# ArtFire.net
KiCad netlist of a schematic drawn in Altium Designer
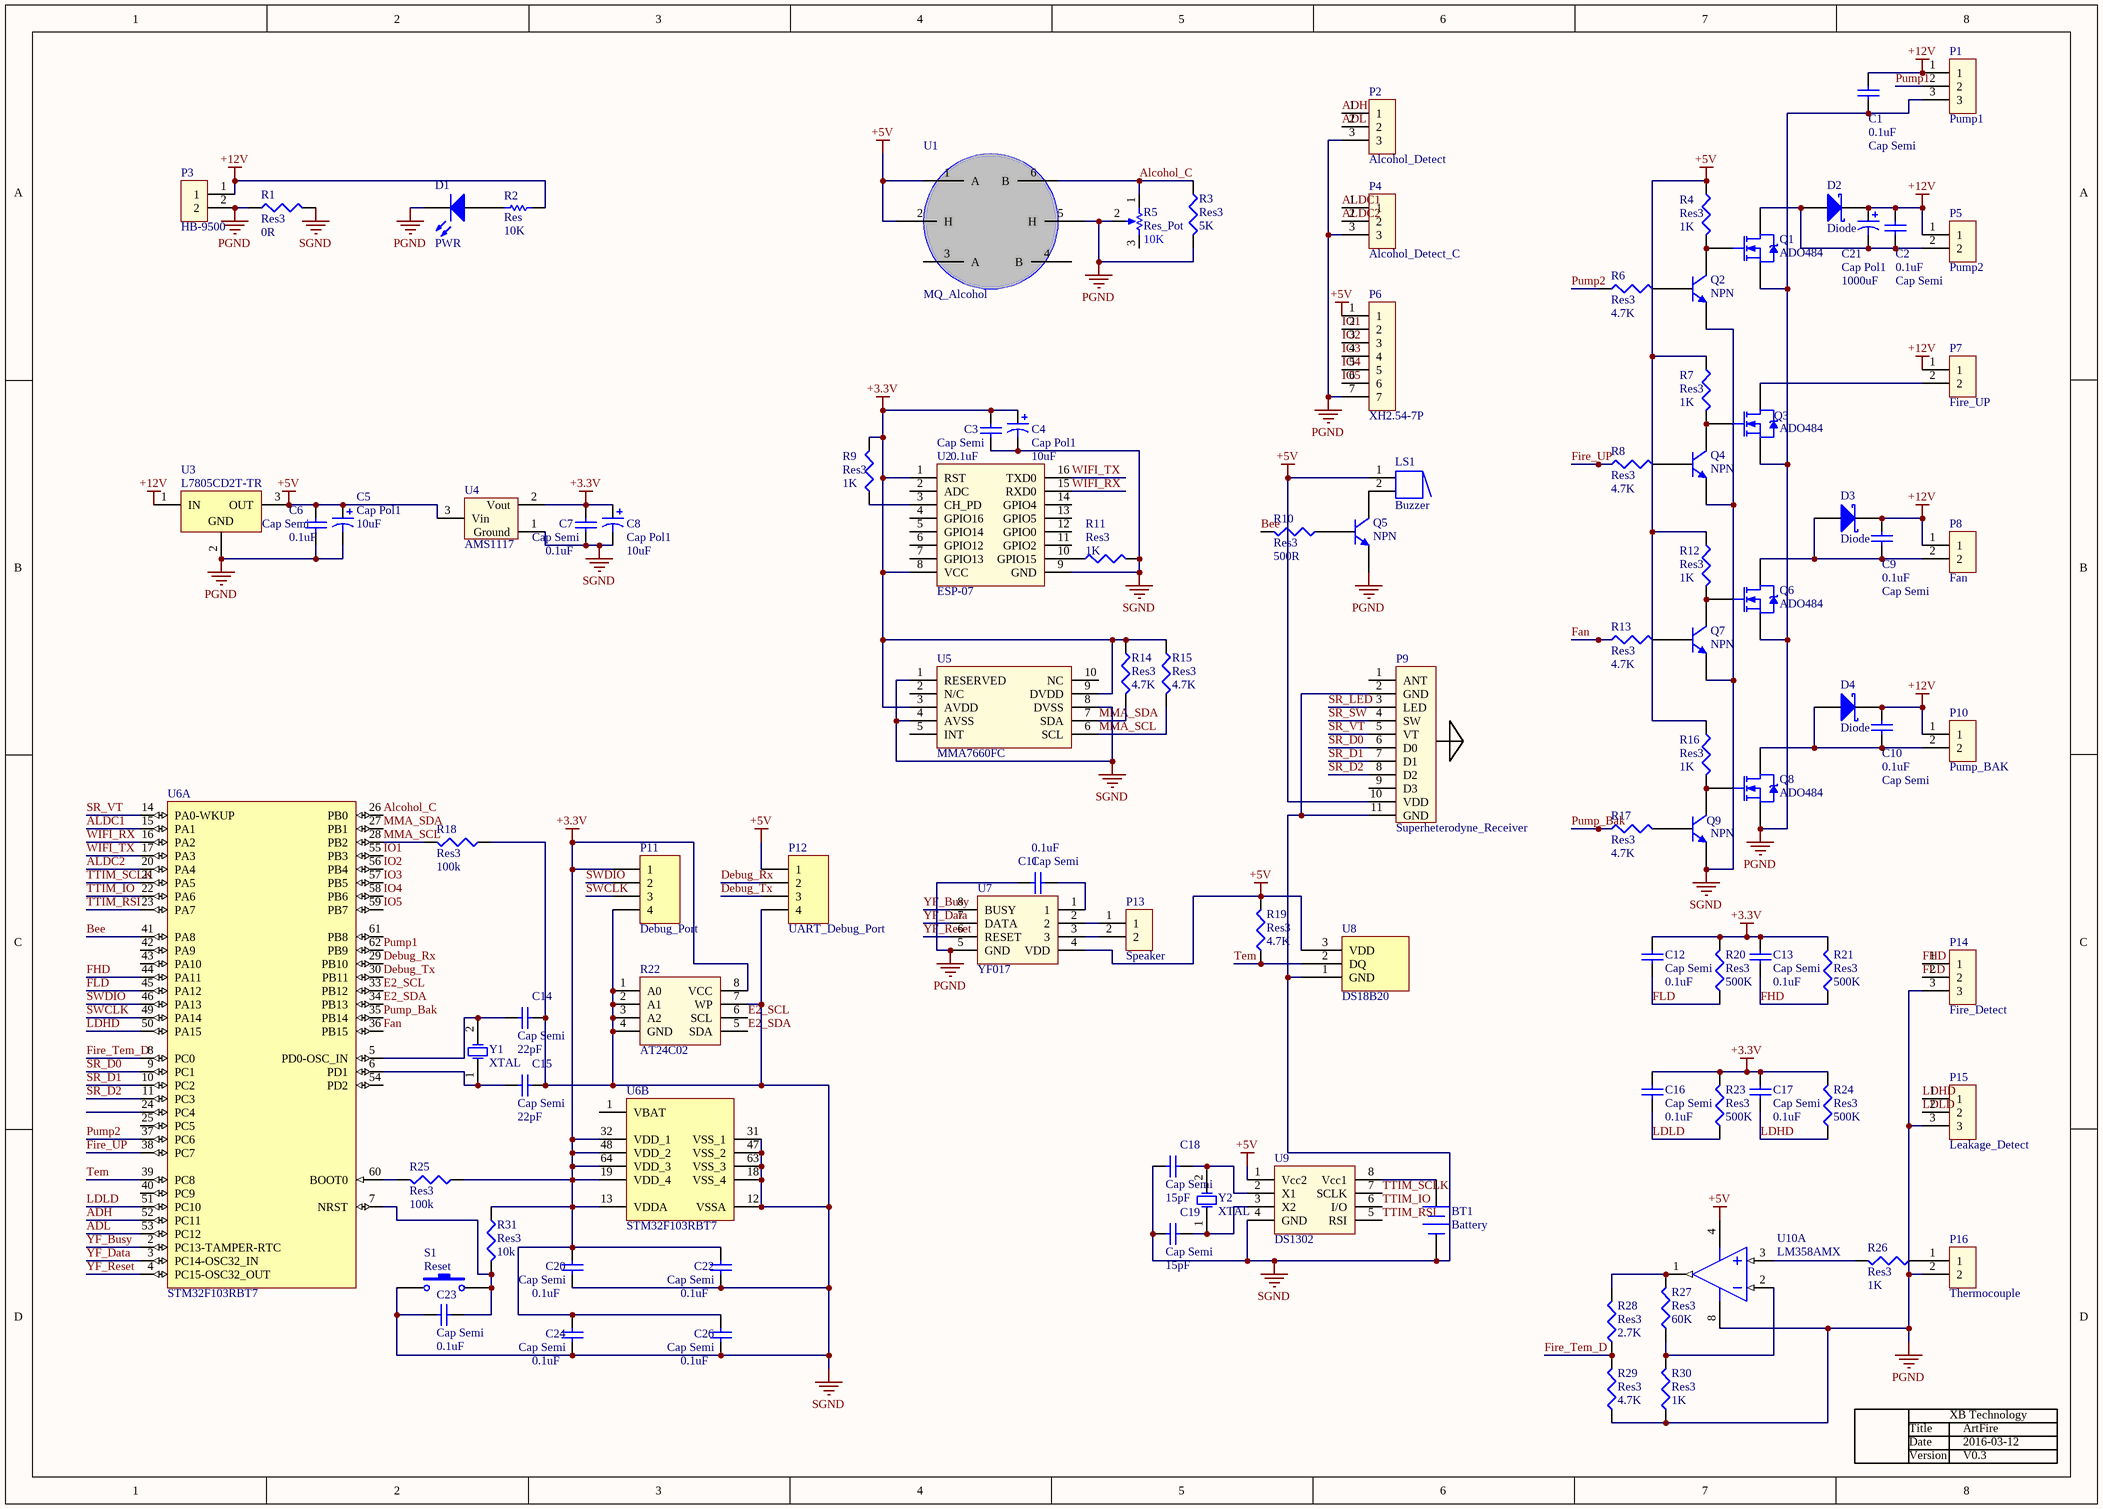
[diagram p0: ArtFire.SchDoc]

(export (version "E")
  (design (tool "Eeschema 10.0.6"))
  (components
    (comp (ref "BT1")
      (value "Battery")
      (footprint "Battery_1302")
      (description "Multicell Battery")
      (fields (field (name "PUBLISHER") "Altium Limited"))
      (libsource (lib "Miscellaneous Devices") (part "Battery"))
    )
    (comp (ref "C1")
      (value "Cap Semi")
      (footprint "6-0805_N")
      (description "Capacitor (Semiconductor SIM Model)")
      (fields (field (name "ALTIUM_VALUE") "0.1uF") (field (name "PUBLISHER") "Altium Limited"))
      (libsource (lib "Miscellaneous Devices") (part "Cap Semi"))
    )
    (comp (ref "C2")
      (value "Cap Semi")
      (footprint "6-0805_N")
      (description "Capacitor (Semiconductor SIM Model)")
      (fields (field (name "ALTIUM_VALUE") "0.1uF") (field (name "PUBLISHER") "Altium Limited"))
      (libsource (lib "Miscellaneous Devices") (part "Cap Semi"))
    )
    (comp (ref "C3")
      (value "Cap Semi")
      (footprint "6-0805_N")
      (description "Capacitor (Semiconductor SIM Model)")
      (fields (field (name "ALTIUM_VALUE") "0.1uF") (field (name "PUBLISHER") "Altium Limited"))
      (libsource (lib "Miscellaneous Devices") (part "Cap Semi"))
    )
    (comp (ref "C4")
      (value "Cap Pol1")
      (footprint "Cap_5*4mm")
      (description "Polarized Capacitor (Radial)")
      (fields (field (name "ALTIUM_VALUE") "10uF") (field (name "PUBLISHER") "Altium Limited"))
      (libsource (lib "Miscellaneous Devices") (part "Cap Pol1"))
    )
    (comp (ref "C5")
      (value "Cap Pol1")
      (footprint "Cap_5*4mm")
      (description "Polarized Capacitor (Radial)")
      (fields (field (name "ALTIUM_VALUE") "10uF") (field (name "PUBLISHER") "Altium Limited"))
      (libsource (lib "Miscellaneous Devices") (part "Cap Pol1"))
    )
    (comp (ref "C6")
      (value "Cap Semi")
      (footprint "6-0805_N")
      (description "Capacitor (Semiconductor SIM Model)")
      (fields (field (name "ALTIUM_VALUE") "0.1uF") (field (name "PUBLISHER") "Altium Limited"))
      (libsource (lib "Miscellaneous Devices") (part "Cap Semi"))
    )
    (comp (ref "C7")
      (value "Cap Semi")
      (footprint "6-0805_N")
      (description "Capacitor (Semiconductor SIM Model)")
      (fields (field (name "ALTIUM_VALUE") "0.1uF") (field (name "PUBLISHER") "Altium Limited"))
      (libsource (lib "Miscellaneous Devices") (part "Cap Semi"))
    )
    (comp (ref "C8")
      (value "Cap Pol1")
      (footprint "Cap_5*4mm")
      (description "Polarized Capacitor (Radial)")
      (fields (field (name "ALTIUM_VALUE") "10uF") (field (name "PUBLISHER") "Altium Limited"))
      (libsource (lib "Miscellaneous Devices") (part "Cap Pol1"))
    )
    (comp (ref "C9")
      (value "Cap Semi")
      (footprint "6-0805_N")
      (description "Capacitor (Semiconductor SIM Model)")
      (fields (field (name "ALTIUM_VALUE") "0.1uF") (field (name "PUBLISHER") "Altium Limited"))
      (libsource (lib "Miscellaneous Devices") (part "Cap Semi"))
    )
    (comp (ref "C10")
      (value "Cap Semi")
      (footprint "6-0805_N")
      (description "Capacitor (Semiconductor SIM Model)")
      (fields (field (name "ALTIUM_VALUE") "0.1uF") (field (name "PUBLISHER") "Altium Limited"))
      (libsource (lib "Miscellaneous Devices") (part "Cap Semi"))
    )
    (comp (ref "C11")
      (value "Cap Semi")
      (footprint "6-0805_N")
      (description "Capacitor (Semiconductor SIM Model)")
      (fields (field (name "ALTIUM_VALUE") "0.1uF") (field (name "PUBLISHER") "Altium Limited"))
      (libsource (lib "Miscellaneous Devices") (part "Cap Semi"))
    )
    (comp (ref "C12")
      (value "Cap Semi")
      (footprint "6-0805_N")
      (description "Capacitor (Semiconductor SIM Model)")
      (fields (field (name "ALTIUM_VALUE") "0.1uF") (field (name "PUBLISHER") "Altium Limited"))
      (libsource (lib "Miscellaneous Devices") (part "Cap Semi"))
    )
    (comp (ref "C13")
      (value "Cap Semi")
      (footprint "6-0805_N")
      (description "Capacitor (Semiconductor SIM Model)")
      (fields (field (name "ALTIUM_VALUE") "0.1uF") (field (name "PUBLISHER") "Altium Limited"))
      (libsource (lib "Miscellaneous Devices") (part "Cap Semi"))
    )
    (comp (ref "C14")
      (value "Cap Semi")
      (footprint "6-0805_N")
      (description "Capacitor (Semiconductor SIM Model)")
      (fields (field (name "ALTIUM_VALUE") "22pF") (field (name "PUBLISHER") "Altium Limited"))
      (libsource (lib "Miscellaneous Devices") (part "Cap Semi"))
    )
    (comp (ref "C15")
      (value "Cap Semi")
      (footprint "6-0805_N")
      (description "Capacitor (Semiconductor SIM Model)")
      (fields (field (name "ALTIUM_VALUE") "22pF") (field (name "PUBLISHER") "Altium Limited"))
      (libsource (lib "Miscellaneous Devices") (part "Cap Semi"))
    )
    (comp (ref "C16")
      (value "Cap Semi")
      (footprint "6-0805_N")
      (description "Capacitor (Semiconductor SIM Model)")
      (fields (field (name "ALTIUM_VALUE") "0.1uF") (field (name "PUBLISHER") "Altium Limited"))
      (libsource (lib "Miscellaneous Devices") (part "Cap Semi"))
    )
    (comp (ref "C17")
      (value "Cap Semi")
      (footprint "6-0805_N")
      (description "Capacitor (Semiconductor SIM Model)")
      (fields (field (name "ALTIUM_VALUE") "0.1uF") (field (name "PUBLISHER") "Altium Limited"))
      (libsource (lib "Miscellaneous Devices") (part "Cap Semi"))
    )
    (comp (ref "C18")
      (value "Cap Semi")
      (footprint "6-0805_N")
      (description "Capacitor (Semiconductor SIM Model)")
      (fields (field (name "ALTIUM_VALUE") "15pF") (field (name "PUBLISHER") "Altium Limited"))
      (libsource (lib "Miscellaneous Devices") (part "Cap Semi"))
    )
    (comp (ref "C19")
      (value "Cap Semi")
      (footprint "6-0805_N")
      (description "Capacitor (Semiconductor SIM Model)")
      (fields (field (name "ALTIUM_VALUE") "15pF") (field (name "PUBLISHER") "Altium Limited"))
      (libsource (lib "Miscellaneous Devices") (part "Cap Semi"))
    )
    (comp (ref "C20")
      (value "Cap Semi")
      (footprint "6-0805_N")
      (description "Capacitor (Semiconductor SIM Model)")
      (fields (field (name "ALTIUM_VALUE") "0.1uF") (field (name "PUBLISHER") "Altium Limited"))
      (libsource (lib "Miscellaneous Devices") (part "Cap Semi"))
    )
    (comp (ref "C21")
      (value "Cap Pol1")
      (footprint "CAP_10*10MM")
      (description "Polarized Capacitor (Radial)")
      (fields (field (name "ALTIUM_VALUE") "1000uF") (field (name "PUBLISHER") "Altium Limited"))
      (libsource (lib "Miscellaneous Devices") (part "Cap Pol1"))
    )
    (comp (ref "C22")
      (value "Cap Semi")
      (footprint "6-0805_N")
      (description "Capacitor (Semiconductor SIM Model)")
      (fields (field (name "ALTIUM_VALUE") "0.1uF") (field (name "PUBLISHER") "Altium Limited"))
      (libsource (lib "Miscellaneous Devices") (part "Cap Semi"))
    )
    (comp (ref "C23")
      (value "Cap Semi")
      (footprint "6-0805_N")
      (description "Capacitor (Semiconductor SIM Model)")
      (fields (field (name "ALTIUM_VALUE") "0.1uF") (field (name "PUBLISHER") "Altium Limited"))
      (libsource (lib "Miscellaneous Devices") (part "Cap Semi"))
    )
    (comp (ref "C24")
      (value "Cap Semi")
      (footprint "6-0805_N")
      (description "Capacitor (Semiconductor SIM Model)")
      (fields (field (name "ALTIUM_VALUE") "0.1uF") (field (name "PUBLISHER") "Altium Limited"))
      (libsource (lib "Miscellaneous Devices") (part "Cap Semi"))
    )
    (comp (ref "C26")
      (value "Cap Semi")
      (footprint "6-0805_N")
      (description "Capacitor (Semiconductor SIM Model)")
      (fields (field (name "ALTIUM_VALUE") "0.1uF") (field (name "PUBLISHER") "Altium Limited"))
      (libsource (lib "Miscellaneous Devices") (part "Cap Semi"))
    )
    (comp (ref "D1")
      (value "PWR")
      (footprint "6-0805_N")
      (description "Typical INFRARED GaAs LED")
      (fields (field (name "PUBLISHER") "Altium Limited"))
      (libsource (lib "Miscellaneous Devices") (part "LED0"))
    )
    (comp (ref "D2")
      (value "Diode")
      (footprint "US1M")
      (description "Silicon RF Schottky Diode for Mixer Applications in the VHF/UHF Range")
      (fields (field (name "PUBLISHER") "Altium Limited"))
      (libsource (lib "Miscellaneous Devices") (part "Diode BAT17"))
    )
    (comp (ref "D3")
      (value "Diode")
      (footprint "US1M")
      (description "Silicon RF Schottky Diode for Mixer Applications in the VHF/UHF Range")
      (fields (field (name "PUBLISHER") "Altium Limited"))
      (libsource (lib "Miscellaneous Devices") (part "Diode BAT17"))
    )
    (comp (ref "D4")
      (value "Diode")
      (footprint "US1M")
      (description "Silicon RF Schottky Diode for Mixer Applications in the VHF/UHF Range")
      (fields (field (name "PUBLISHER") "Altium Limited"))
      (libsource (lib "Miscellaneous Devices") (part "Diode BAT17"))
    )
    (comp (ref "LS1")
      (value "Buzzer")
      (footprint "BUZZER")
      (description "Magnetic Transducer Buzzer")
      (fields (field (name "PUBLISHER") "Altium Limited"))
      (libsource (lib "Miscellaneous Devices") (part "Buzzer"))
    )
    (comp (ref "P1") (value "Pump1") (footprint "XH2.54-3P") (libsource (lib "XH2.54") (part "XH2.54-3P")))
    (comp (ref "P2")
      (value "Alcohol_Detect")
      (footprint "XH2.54-3P")
      (libsource (lib "XH2.54") (part "XH2.54-3P"))
    )
    (comp (ref "P3")
      (value "HB-9500")
      (footprint "HB-9500")
      (description "High current connector")
      (libsource (lib "Simon'Library") (part "HB-9500"))
    )
    (comp (ref "P4")
      (value "Alcohol_Detect_C")
      (footprint "XH2.54-3P")
      (libsource (lib "XH2.54") (part "XH2.54-3P"))
    )
    (comp (ref "P5") (value "Pump2") (footprint "CH3.96_2P") (libsource (lib "CH3.96") (part "CH3.96_2P")))
    (comp (ref "P6")
      (value "XH2.54-7P")
      (footprint "XH2.54-7P")
      (libsource (lib "XH2.54") (part "XH2.54-7P"))
    )
    (comp (ref "P7") (value "Fire_UP") (footprint "KF3.96_2P") (libsource (lib "KF3.96") (part "KF3.96")))
    (comp (ref "P8") (value "Fan") (footprint "XH2.54-2P") (libsource (lib "XH2.54") (part "XH2.54-2P")))
    (comp (ref "P9")
      (value "Superheterodyne_Receiver")
      (footprint "Sperheterodyne_Receiver")
      (libsource (lib "Simon'Library") (part "Superheterodyne_Receiver"))
    )
    (comp (ref "P10")
      (value "Pump_BAK")
      (footprint "CH3.96_2P")
      (libsource (lib "CH3.96") (part "CH3.96_2P"))
    )
    (comp (ref "P11")
      (value "Debug_Port")
      (footprint "HDR1X4")
      (description "Header, 4-Pin")
      (fields (field (name "PUBLISHER") "Altium Limited"))
      (libsource (lib "Miscellaneous Connectors") (part "Header 4"))
    )
    (comp (ref "P12")
      (value "UART_Debug_Port")
      (footprint "HDR1X4")
      (description "Header, 4-Pin")
      (fields (field (name "PUBLISHER") "Altium Limited"))
      (libsource (lib "Miscellaneous Connectors") (part "Header 4"))
    )
    (comp (ref "P13") (value "Speaker") (footprint "XH2.54-2P") (libsource (lib "XH2.54") (part "XH2.54-2P")))
    (comp (ref "P14")
      (value "Fire_Detect")
      (footprint "CH3.96_3P")
      (libsource (lib "CH3.96") (part "CH3.96_3P"))
    )
    (comp (ref "P15")
      (value "Leakage_Detect")
      (footprint "XH2.54-3P")
      (libsource (lib "XH2.54") (part "XH2.54-3P"))
    )
    (comp (ref "P16")
      (value "Thermocouple")
      (footprint "CH3.96_2P")
      (libsource (lib "CH3.96") (part "CH3.96_2P"))
    )
    (comp (ref "Q1")
      (value "ADO484")
      (footprint "D2PAK_N")
      (description "N-Channel Power MOSFET")
      (fields (field (name "PUBLISHER") "Altium Limited"))
      (libsource (lib "Miscellaneous Devices") (part "NMOS-2"))
    )
    (comp (ref "Q2")
      (value "NPN")
      (footprint "SOT-23_N")
      (description "NPN Bipolar Transistor")
      (fields (field (name "PUBLISHER") "Altium Limited"))
      (libsource (lib "Miscellaneous Devices") (part "NPN"))
    )
    (comp (ref "Q3")
      (value "ADO484")
      (footprint "D2PAK_N")
      (description "N-Channel Power MOSFET")
      (fields (field (name "PUBLISHER") "Altium Limited"))
      (libsource (lib "Miscellaneous Devices") (part "NMOS-2"))
    )
    (comp (ref "Q4")
      (value "NPN")
      (footprint "SOT-23_N")
      (description "NPN Bipolar Transistor")
      (fields (field (name "PUBLISHER") "Altium Limited"))
      (libsource (lib "Miscellaneous Devices") (part "NPN"))
    )
    (comp (ref "Q5")
      (value "NPN")
      (footprint "SOT-23_N")
      (description "NPN Bipolar Transistor")
      (fields (field (name "PUBLISHER") "Altium Limited"))
      (libsource (lib "Miscellaneous Devices") (part "NPN"))
    )
    (comp (ref "Q6")
      (value "ADO484")
      (footprint "D2PAK_N")
      (description "N-Channel Power MOSFET")
      (fields (field (name "PUBLISHER") "Altium Limited"))
      (libsource (lib "Miscellaneous Devices") (part "NMOS-2"))
    )
    (comp (ref "Q7")
      (value "NPN")
      (footprint "SOT-23_N")
      (description "NPN Bipolar Transistor")
      (fields (field (name "PUBLISHER") "Altium Limited"))
      (libsource (lib "Miscellaneous Devices") (part "NPN"))
    )
    (comp (ref "Q8")
      (value "ADO484")
      (footprint "D2PAK_N")
      (description "N-Channel Power MOSFET")
      (fields (field (name "PUBLISHER") "Altium Limited"))
      (libsource (lib "Miscellaneous Devices") (part "NMOS-2"))
    )
    (comp (ref "Q9")
      (value "NPN")
      (footprint "SOT-23_N")
      (description "NPN Bipolar Transistor")
      (fields (field (name "PUBLISHER") "Altium Limited"))
      (libsource (lib "Miscellaneous Devices") (part "NPN"))
    )
    (comp (ref "R1")
      (value "Res3")
      (footprint "6-0805_N")
      (description "Resistor")
      (fields (field (name "ALTIUM_VALUE") "0R") (field (name "PUBLISHER") "Altium Limited"))
      (libsource (lib "Miscellaneous Devices") (part "Res3"))
    )
    (comp (ref "R2")
      (value "Res")
      (footprint "6-0805_N")
      (description "Resistor")
      (fields (field (name "ALTIUM_VALUE") "10K") (field (name "PUBLISHER") "Altium Limited"))
      (libsource (lib "Miscellaneous Devices") (part "Res1"))
    )
    (comp (ref "R3")
      (value "Res3")
      (footprint "6-0805_N")
      (description "Resistor")
      (fields (field (name "ALTIUM_VALUE") "5K") (field (name "PUBLISHER") "Altium Limited"))
      (libsource (lib "Miscellaneous Devices") (part "Res3"))
    )
    (comp (ref "R4")
      (value "Res3")
      (footprint "6-0805_N")
      (description "Resistor")
      (fields (field (name "ALTIUM_VALUE") "1K") (field (name "PUBLISHER") "Altium Limited"))
      (libsource (lib "Miscellaneous Devices") (part "Res3"))
    )
    (comp (ref "R5")
      (value "Res_Pot")
      (footprint "VR5")
      (fields (field (name "RES_V") "10K"))
      (libsource (lib "Simon'Library") (part "Res_Pot"))
    )
    (comp (ref "R6")
      (value "Res3")
      (footprint "6-0805_N")
      (description "Resistor")
      (fields (field (name "ALTIUM_VALUE") "4.7K") (field (name "PUBLISHER") "Altium Limited"))
      (libsource (lib "Miscellaneous Devices") (part "Res3"))
    )
    (comp (ref "R7")
      (value "Res3")
      (footprint "6-0805_N")
      (description "Resistor")
      (fields (field (name "ALTIUM_VALUE") "1K") (field (name "PUBLISHER") "Altium Limited"))
      (libsource (lib "Miscellaneous Devices") (part "Res3"))
    )
    (comp (ref "R8")
      (value "Res3")
      (footprint "6-0805_N")
      (description "Resistor")
      (fields (field (name "ALTIUM_VALUE") "4.7K") (field (name "PUBLISHER") "Altium Limited"))
      (libsource (lib "Miscellaneous Devices") (part "Res3"))
    )
    (comp (ref "R9")
      (value "Res3")
      (footprint "6-0805_N")
      (description "Resistor")
      (fields (field (name "ALTIUM_VALUE") "1K") (field (name "PUBLISHER") "Altium Limited"))
      (libsource (lib "Miscellaneous Devices") (part "Res3"))
    )
    (comp (ref "R10")
      (value "Res3")
      (footprint "6-0805_N")
      (description "Resistor")
      (fields (field (name "ALTIUM_VALUE") "500R") (field (name "PUBLISHER") "Altium Limited"))
      (libsource (lib "Miscellaneous Devices") (part "Res3"))
    )
    (comp (ref "R11")
      (value "Res3")
      (footprint "6-0805_N")
      (description "Resistor")
      (fields (field (name "ALTIUM_VALUE") "1K") (field (name "PUBLISHER") "Altium Limited"))
      (libsource (lib "Miscellaneous Devices") (part "Res3"))
    )
    (comp (ref "R12")
      (value "Res3")
      (footprint "6-0805_N")
      (description "Resistor")
      (fields (field (name "ALTIUM_VALUE") "1K") (field (name "PUBLISHER") "Altium Limited"))
      (libsource (lib "Miscellaneous Devices") (part "Res3"))
    )
    (comp (ref "R13")
      (value "Res3")
      (footprint "6-0805_N")
      (description "Resistor")
      (fields (field (name "ALTIUM_VALUE") "4.7K") (field (name "PUBLISHER") "Altium Limited"))
      (libsource (lib "Miscellaneous Devices") (part "Res3"))
    )
    (comp (ref "R14")
      (value "Res3")
      (footprint "6-0805_N")
      (description "Resistor")
      (fields (field (name "ALTIUM_VALUE") "4.7K") (field (name "PUBLISHER") "Altium Limited"))
      (libsource (lib "Miscellaneous Devices") (part "Res3"))
    )
    (comp (ref "R15")
      (value "Res3")
      (footprint "6-0805_N")
      (description "Resistor")
      (fields (field (name "ALTIUM_VALUE") "4.7K") (field (name "PUBLISHER") "Altium Limited"))
      (libsource (lib "Miscellaneous Devices") (part "Res3"))
    )
    (comp (ref "R16")
      (value "Res3")
      (footprint "6-0805_N")
      (description "Resistor")
      (fields (field (name "ALTIUM_VALUE") "1K") (field (name "PUBLISHER") "Altium Limited"))
      (libsource (lib "Miscellaneous Devices") (part "Res3"))
    )
    (comp (ref "R17")
      (value "Res3")
      (footprint "6-0805_N")
      (description "Resistor")
      (fields (field (name "ALTIUM_VALUE") "4.7K") (field (name "PUBLISHER") "Altium Limited"))
      (libsource (lib "Miscellaneous Devices") (part "Res3"))
    )
    (comp (ref "R18")
      (value "Res3")
      (footprint "6-0805_N")
      (description "Resistor")
      (fields (field (name "ALTIUM_VALUE") "100k") (field (name "PUBLISHER") "Altium Limited"))
      (libsource (lib "Miscellaneous Devices") (part "Res3"))
    )
    (comp (ref "R19")
      (value "Res3")
      (footprint "6-0805_N")
      (description "Resistor")
      (fields (field (name "ALTIUM_VALUE") "4.7K") (field (name "PUBLISHER") "Altium Limited"))
      (libsource (lib "Miscellaneous Devices") (part "Res3"))
    )
    (comp (ref "R20")
      (value "Res3")
      (footprint "6-0805_N")
      (description "Resistor")
      (fields (field (name "ALTIUM_VALUE") "500K") (field (name "PUBLISHER") "Altium Limited"))
      (libsource (lib "Miscellaneous Devices") (part "Res3"))
    )
    (comp (ref "R21")
      (value "Res3")
      (footprint "6-0805_N")
      (description "Resistor")
      (fields (field (name "ALTIUM_VALUE") "500K") (field (name "PUBLISHER") "Altium Limited"))
      (libsource (lib "Miscellaneous Devices") (part "Res3"))
    )
    (comp (ref "R22")
      (value "AT24C02")
      (footprint "SOP8_TDA2822")
      (libsource (lib "Simon'Library") (part "AT24C02"))
    )
    (comp (ref "R23")
      (value "Res3")
      (footprint "6-0805_N")
      (description "Resistor")
      (fields (field (name "ALTIUM_VALUE") "500K") (field (name "PUBLISHER") "Altium Limited"))
      (libsource (lib "Miscellaneous Devices") (part "Res3"))
    )
    (comp (ref "R24")
      (value "Res3")
      (footprint "6-0805_N")
      (description "Resistor")
      (fields (field (name "ALTIUM_VALUE") "500K") (field (name "PUBLISHER") "Altium Limited"))
      (libsource (lib "Miscellaneous Devices") (part "Res3"))
    )
    (comp (ref "R25")
      (value "Res3")
      (footprint "6-0805_N")
      (description "Resistor")
      (fields (field (name "ALTIUM_VALUE") "100k") (field (name "PUBLISHER") "Altium Limited"))
      (libsource (lib "Miscellaneous Devices") (part "Res3"))
    )
    (comp (ref "R26")
      (value "Res3")
      (footprint "6-0805_N")
      (description "Resistor")
      (fields (field (name "ALTIUM_VALUE") "1K") (field (name "PUBLISHER") "Altium Limited"))
      (libsource (lib "Miscellaneous Devices") (part "Res3"))
    )
    (comp (ref "R27")
      (value "Res3")
      (footprint "6-0805_N")
      (description "Resistor")
      (fields (field (name "ALTIUM_VALUE") "60K") (field (name "PUBLISHER") "Altium Limited"))
      (libsource (lib "Miscellaneous Devices") (part "Res3"))
    )
    (comp (ref "R28")
      (value "Res3")
      (footprint "6-0805_N")
      (description "Resistor")
      (fields (field (name "ALTIUM_VALUE") "2.7K") (field (name "PUBLISHER") "Altium Limited"))
      (libsource (lib "Miscellaneous Devices") (part "Res3"))
    )
    (comp (ref "R29")
      (value "Res3")
      (footprint "6-0805_N")
      (description "Resistor")
      (fields (field (name "ALTIUM_VALUE") "4.7K") (field (name "PUBLISHER") "Altium Limited"))
      (libsource (lib "Miscellaneous Devices") (part "Res3"))
    )
    (comp (ref "R30")
      (value "Res3")
      (footprint "6-0805_N")
      (description "Resistor")
      (fields (field (name "ALTIUM_VALUE") "1K") (field (name "PUBLISHER") "Altium Limited"))
      (libsource (lib "Miscellaneous Devices") (part "Res3"))
    )
    (comp (ref "R31")
      (value "Res3")
      (footprint "6-0805_N")
      (description "Resistor")
      (fields (field (name "ALTIUM_VALUE") "10k") (field (name "PUBLISHER") "Altium Limited"))
      (libsource (lib "Miscellaneous Devices") (part "Res3"))
    )
    (comp (ref "S1")
      (value "Reset")
      (footprint "SWP_PB_6.5mm")
      (description "Switch")
      (fields (field (name "PUBLISHER") "Altium Limited"))
      (libsource (lib "Miscellaneous Devices") (part "SW-PB"))
    )
    (comp (ref "U1") (value "MQ_Alcohol") (footprint "MQ") (libsource (lib "Simon'Library") (part "MQ")))
    (comp (ref "U2")
      (value "ESP-07")
      (footprint "ESP-07_Wifi")
      (libsource (lib "Simon'Library") (part "ESP-07_Wifi"))
    )
    (comp (ref "U3")
      (value "L7805CD2T-TR")
      (footprint "D2PAK_N")
      (description "Positive Voltage Regulator, 5V, 3-Pin TO-220")
      (libsource (lib "altium-import") (part "root_0_PM-REG-L4940-SIL3_"))
    )
    (comp (ref "U4")
      (value "AMS1117")
      (footprint "SOT223_N")
      (libsource (lib "Simon'Library") (part "AMS1117"))
    )
    (comp (ref "U5")
      (value "MMA7660FC")
      (footprint "DFN-10P")
      (libsource (lib "Simon'Library") (part "MMA7660FC"))
    )
    (comp (ref "U6")
      (value "STM32F103RBT7")
      (footprint "LQFP64_L")
      (libsource (lib "Altium Content Vault") (part "MC-ARM-STM32F101-SQ64"))
    )
    (comp (ref "U7") (value "YF017") (footprint "DIP-8") (libsource (lib "Simon'Library") (part "YF017")))
    (comp (ref "U8")
      (value "DS18B20")
      (footprint "TO-92A")
      (libsource (lib "Simon'Library") (part "DS18B20"))
    )
    (comp (ref "U9")
      (value "DS1302")
      (footprint "SOP8_TDA2822")
      (libsource (lib "Simon'Library") (part "DS1302"))
    )
    (comp (ref "U10")
      (value "LM358AMX")
      (footprint "M08A_M")
      (description "Low Power Dual Operational Amplifier, 8-pin Narrow SOIC")
      (fields (field (name "MANUFACTURER") "National Semiconductor"))
      (libsource (lib "Altium Content Vault") (part "AMP-OPA-LM158-8"))
    )
    (comp (ref "Y1")
      (value "XTAL")
      (footprint "XTAL")
      (description "Crystal Oscillator")
      (fields (field (name "PUBLISHER") "Altium Limited"))
      (libsource (lib "Miscellaneous Devices") (part "XTAL"))
    )
    (comp (ref "Y2")
      (value "XTAL")
      (footprint "32.768Cystal")
      (description "Crystal Oscillator")
      (fields (field (name "PUBLISHER") "Altium Limited"))
      (libsource (lib "Miscellaneous Devices") (part "XTAL"))
    )
  )
  (nets
    (net (code "1") (name "+3.3V") (class "Default")
      (node (ref "C12") (pin "2") (pinfunction "2_2") (pintype "passive"))
      (node (ref "C13") (pin "2") (pinfunction "2_2") (pintype "passive"))
      (node (ref "C16") (pin "2") (pinfunction "2_2") (pintype "passive"))
      (node (ref "C17") (pin "2") (pinfunction "2_2") (pintype "passive"))
      (node (ref "C20") (pin "1") (pinfunction "1_1") (pintype "passive"))
      (node (ref "C22") (pin "1") (pinfunction "1_1") (pintype "passive"))
      (node (ref "C24") (pin "1") (pinfunction "1_1") (pintype "passive"))
      (node (ref "C26") (pin "1") (pinfunction "1_1") (pintype "passive"))
      (node (ref "C3") (pin "1") (pinfunction "1_1") (pintype "passive"))
      (node (ref "C4") (pin "1") (pinfunction "1_1") (pintype "passive"))
      (node (ref "C7") (pin "1") (pinfunction "1_1") (pintype "passive"))
      (node (ref "C8") (pin "1") (pinfunction "1_1") (pintype "passive"))
      (node (ref "P11") (pin "1") (pinfunction "1_1") (pintype "passive"))
      (node (ref "R14") (pin "1") (pinfunction "1_1") (pintype "passive"))
      (node (ref "R15") (pin "1") (pinfunction "1_1") (pintype "passive"))
      (node (ref "R20") (pin "2") (pinfunction "2_2") (pintype "passive"))
      (node (ref "R21") (pin "2") (pinfunction "2_2") (pintype "passive"))
      (node (ref "R22") (pin "8") (pinfunction "VCC_8") (pintype "passive"))
      (node (ref "R23") (pin "2") (pinfunction "2_2") (pintype "passive"))
      (node (ref "R24") (pin "2") (pinfunction "2_2") (pintype "passive"))
      (node (ref "R25") (pin "1") (pinfunction "1_1") (pintype "passive"))
      (node (ref "R31") (pin "1") (pinfunction "1_1") (pintype "passive"))
      (node (ref "R9") (pin "2") (pinfunction "2_2") (pintype "passive"))
      (node (ref "U2") (pin "1") (pinfunction "RST_1") (pintype "passive"))
      (node (ref "U2") (pin "8") (pinfunction "VCC_8") (pintype "passive"))
      (node (ref "U4") (pin "2") (pinfunction "Vout_2") (pintype "passive"))
      (node (ref "U5") (pin "3") (pinfunction "AVDD_3") (pintype "passive"))
      (node (ref "U5") (pin "9") (pinfunction "DVDD_9") (pintype "passive"))
      (node (ref "U6") (pin "13") (pinfunction "VDDA_13") (pintype "power_in"))
      (node (ref "U6") (pin "19") (pinfunction "VDD_4_19") (pintype "power_in"))
      (node (ref "U6") (pin "32") (pinfunction "VDD_1_32") (pintype "power_in"))
      (node (ref "U6") (pin "48") (pinfunction "VDD_2_48") (pintype "power_in"))
      (node (ref "U6") (pin "64") (pinfunction "VDD_3_64") (pintype "power_in"))
    )
    (net (code "2") (name "+5V") (class "Default")
      (node (ref "C5") (pin "1") (pinfunction "1_1") (pintype "passive"))
      (node (ref "C6") (pin "1") (pinfunction "1_1") (pintype "passive"))
      (node (ref "LS1") (pin "1") (pinfunction "1_1") (pintype "passive"))
      (node (ref "P12") (pin "1") (pinfunction "1_1") (pintype "passive"))
      (node (ref "P6") (pin "1") (pinfunction "1_1") (pintype "passive"))
      (node (ref "P9") (pin "10") (pinfunction "VDD_10") (pintype "passive"))
      (node (ref "R12") (pin "1") (pinfunction "1_1") (pintype "passive"))
      (node (ref "R16") (pin "1") (pinfunction "1_1") (pintype "passive"))
      (node (ref "R19") (pin "2") (pinfunction "2_2") (pintype "passive"))
      (node (ref "R4") (pin "1") (pinfunction "1_1") (pintype "passive"))
      (node (ref "R7") (pin "1") (pinfunction "1_1") (pintype "passive"))
      (node (ref "U1") (pin "1") (pinfunction "A_1") (pintype "passive"))
      (node (ref "U1") (pin "2") (pinfunction "H_2") (pintype "passive"))
      (node (ref "U10") (pin "4") (pinfunction "GND_4") (pintype "power_in"))
      (node (ref "U3") (pin "3") (pinfunction "OUT_3") (pintype "power_in"))
      (node (ref "U4") (pin "3") (pinfunction "Vin_3") (pintype "passive"))
      (node (ref "U7") (pin "4") (pinfunction "VDD_4") (pintype "passive"))
      (node (ref "U8") (pin "3") (pinfunction "VDD_3") (pintype "passive"))
      (node (ref "U9") (pin "1") (pinfunction "Vcc2_1") (pintype "passive"))
    )
    (net (code "3") (name "+12V") (class "Default")
      (node (ref "C1") (pin "1") (pinfunction "1_1") (pintype "passive"))
      (node (ref "C10") (pin "1") (pinfunction "1_1") (pintype "passive"))
      (node (ref "C2") (pin "1") (pinfunction "1_1") (pintype "passive"))
      (node (ref "C21") (pin "1") (pinfunction "1_1") (pintype "passive"))
      (node (ref "C9") (pin "1") (pinfunction "1_1") (pintype "passive"))
      (node (ref "D2") (pin "2") (pinfunction "K_2") (pintype "passive"))
      (node (ref "D3") (pin "2") (pinfunction "K_2") (pintype "passive"))
      (node (ref "D4") (pin "2") (pinfunction "K_2") (pintype "passive"))
      (node (ref "P1") (pin "1") (pinfunction "1_1") (pintype "passive"))
      (node (ref "P10") (pin "1") (pinfunction "1_1") (pintype "passive"))
      (node (ref "P3") (pin "1") (pinfunction "1_1") (pintype "passive"))
      (node (ref "P5") (pin "1") (pinfunction "1_1") (pintype "passive"))
      (node (ref "P7") (pin "1") (pinfunction "1_1") (pintype "passive"))
      (node (ref "P8") (pin "1") (pinfunction "1_1") (pintype "passive"))
      (node (ref "R2") (pin "2") (pinfunction "2_2") (pintype "passive"))
      (node (ref "U3") (pin "1") (pinfunction "IN_1") (pintype "power_in"))
    )
    (net (code "4") (name "/ADH") (class "Default")
      (node (ref "P2") (pin "1") (pinfunction "1_1") (pintype "passive"))
      (node (ref "U6") (pin "52") (pinfunction "PC11_52") (pintype "bidirectional"))
    )
    (net (code "5") (name "/ADL") (class "Default")
      (node (ref "P2") (pin "2") (pinfunction "2_2") (pintype "passive"))
      (node (ref "U6") (pin "53") (pinfunction "PC12_53") (pintype "bidirectional"))
    )
    (net (code "6") (name "/ALDC1") (class "Default")
      (node (ref "P4") (pin "1") (pinfunction "1_1") (pintype "passive"))
      (node (ref "U6") (pin "15") (pinfunction "PA1_15") (pintype "bidirectional"))
    )
    (net (code "7") (name "/ALDC2") (class "Default")
      (node (ref "P4") (pin "2") (pinfunction "2_2") (pintype "passive"))
      (node (ref "U6") (pin "20") (pinfunction "PA4_20") (pintype "bidirectional"))
    )
    (net (code "8") (name "/Alcohol_C") (class "Default")
      (node (ref "R3") (pin "1") (pinfunction "1_1") (pintype "passive"))
      (node (ref "R5") (pin "1") (pinfunction "TOP_1") (pintype "passive"))
      (node (ref "U1") (pin "6") (pinfunction "B_6") (pintype "passive"))
      (node (ref "U6") (pin "26") (pinfunction "PB0_26") (pintype "bidirectional"))
    )
    (net (code "9") (name "/Bee") (class "Default")
      (node (ref "R10") (pin "2") (pinfunction "2_2") (pintype "passive"))
      (node (ref "U6") (pin "41") (pinfunction "PA8_41") (pintype "bidirectional"))
    )
    (net (code "10") (name "/Debug_Rx") (class "Default")
      (node (ref "P12") (pin "2") (pinfunction "2_2") (pintype "passive"))
      (node (ref "U6") (pin "29") (pinfunction "PB10_29") (pintype "bidirectional"))
    )
    (net (code "11") (name "/Debug_Tx") (class "Default")
      (node (ref "P12") (pin "3") (pinfunction "3_3") (pintype "passive"))
      (node (ref "U6") (pin "30") (pinfunction "PB11_30") (pintype "bidirectional"))
    )
    (net (code "12") (name "/E2_SCL") (class "Default")
      (node (ref "R22") (pin "6") (pinfunction "SCL_6") (pintype "passive"))
      (node (ref "U6") (pin "33") (pinfunction "PB12_33") (pintype "bidirectional"))
    )
    (net (code "13") (name "/E2_SDA") (class "Default")
      (node (ref "R22") (pin "5") (pinfunction "SDA_5") (pintype "passive"))
      (node (ref "U6") (pin "34") (pinfunction "PB13_34") (pintype "bidirectional"))
    )
    (net (code "14") (name "/FHD") (class "Default")
      (node (ref "C13") (pin "1") (pinfunction "1_1") (pintype "passive"))
      (node (ref "P14") (pin "1") (pinfunction "1_1") (pintype "passive"))
      (node (ref "R21") (pin "1") (pinfunction "1_1") (pintype "passive"))
      (node (ref "U6") (pin "44") (pinfunction "PA11_44") (pintype "bidirectional"))
    )
    (net (code "15") (name "/FLD") (class "Default")
      (node (ref "C12") (pin "1") (pinfunction "1_1") (pintype "passive"))
      (node (ref "P14") (pin "2") (pinfunction "2_2") (pintype "passive"))
      (node (ref "R20") (pin "1") (pinfunction "1_1") (pintype "passive"))
      (node (ref "U6") (pin "45") (pinfunction "PA12_45") (pintype "bidirectional"))
    )
    (net (code "16") (name "/Fan") (class "Default")
      (node (ref "R13") (pin "1") (pinfunction "1_1") (pintype "passive"))
      (node (ref "U6") (pin "36") (pinfunction "PB15_36") (pintype "bidirectional"))
    )
    (net (code "17") (name "/Fire_Tem_D") (class "Default")
      (node (ref "R28") (pin "1") (pinfunction "1_1") (pintype "passive"))
      (node (ref "R29") (pin "2") (pinfunction "2_2") (pintype "passive"))
      (node (ref "U6") (pin "8") (pinfunction "PC0_8") (pintype "bidirectional"))
    )
    (net (code "18") (name "/Fire_UP") (class "Default")
      (node (ref "R8") (pin "1") (pinfunction "1_1") (pintype "passive"))
      (node (ref "U6") (pin "38") (pinfunction "PC7_38") (pintype "bidirectional"))
    )
    (net (code "19") (name "/IO1") (class "Default")
      (node (ref "P6") (pin "2") (pinfunction "2_2") (pintype "passive"))
      (node (ref "U6") (pin "55") (pinfunction "PB3_55") (pintype "bidirectional"))
    )
    (net (code "20") (name "/IO2") (class "Default")
      (node (ref "P6") (pin "3") (pinfunction "3_3") (pintype "passive"))
      (node (ref "U6") (pin "56") (pinfunction "PB4_56") (pintype "bidirectional"))
    )
    (net (code "21") (name "/IO3") (class "Default")
      (node (ref "P6") (pin "4") (pinfunction "4_4") (pintype "passive"))
      (node (ref "U6") (pin "57") (pinfunction "PB5_57") (pintype "bidirectional"))
    )
    (net (code "22") (name "/IO4") (class "Default")
      (node (ref "P6") (pin "5") (pinfunction "5_5") (pintype "passive"))
      (node (ref "U6") (pin "58") (pinfunction "PB6_58") (pintype "bidirectional"))
    )
    (net (code "23") (name "/IO5") (class "Default")
      (node (ref "P6") (pin "6") (pinfunction "6_6") (pintype "passive"))
      (node (ref "U6") (pin "59") (pinfunction "PB7_59") (pintype "bidirectional"))
    )
    (net (code "24") (name "/LDHD") (class "Default")
      (node (ref "C17") (pin "1") (pinfunction "1_1") (pintype "passive"))
      (node (ref "P15") (pin "1") (pinfunction "1_1") (pintype "passive"))
      (node (ref "R24") (pin "1") (pinfunction "1_1") (pintype "passive"))
      (node (ref "U6") (pin "50") (pinfunction "PA15_50") (pintype "bidirectional"))
    )
    (net (code "25") (name "/LDLD") (class "Default")
      (node (ref "C16") (pin "1") (pinfunction "1_1") (pintype "passive"))
      (node (ref "P15") (pin "2") (pinfunction "2_2") (pintype "passive"))
      (node (ref "R23") (pin "1") (pinfunction "1_1") (pintype "passive"))
      (node (ref "U6") (pin "51") (pinfunction "PC10_51") (pintype "bidirectional"))
    )
    (net (code "26") (name "/MMA_SCL") (class "Default")
      (node (ref "R15") (pin "2") (pinfunction "2_2") (pintype "passive"))
      (node (ref "R18") (pin "2") (pinfunction "2_2") (pintype "passive"))
      (node (ref "U5") (pin "6") (pinfunction "SCL_6") (pintype "passive"))
      (node (ref "U6") (pin "28") (pinfunction "PB2_28") (pintype "bidirectional"))
    )
    (net (code "27") (name "/MMA_SDA") (class "Default")
      (node (ref "R14") (pin "2") (pinfunction "2_2") (pintype "passive"))
      (node (ref "U5") (pin "7") (pinfunction "SDA_7") (pintype "passive"))
      (node (ref "U6") (pin "27") (pinfunction "PB1_27") (pintype "bidirectional"))
    )
    (net (code "28") (name "/Pump1") (class "Default")
      (node (ref "P1") (pin "2") (pinfunction "2_2") (pintype "passive"))
      (node (ref "U6") (pin "62") (pinfunction "PB9_62") (pintype "bidirectional"))
    )
    (net (code "29") (name "/Pump2") (class "Default")
      (node (ref "R6") (pin "1") (pinfunction "1_1") (pintype "passive"))
      (node (ref "U6") (pin "37") (pinfunction "PC6_37") (pintype "bidirectional"))
    )
    (net (code "30") (name "/Pump_Bak") (class "Default")
      (node (ref "R17") (pin "1") (pinfunction "1_1") (pintype "passive"))
      (node (ref "U6") (pin "35") (pinfunction "PB14_35") (pintype "bidirectional"))
    )
    (net (code "31") (name "/SR_D0") (class "Default")
      (node (ref "P9") (pin "6") (pinfunction "D0_6") (pintype "passive"))
      (node (ref "U6") (pin "9") (pinfunction "PC1_9") (pintype "bidirectional"))
    )
    (net (code "32") (name "/SR_D1") (class "Default")
      (node (ref "P9") (pin "7") (pinfunction "D1_7") (pintype "passive"))
      (node (ref "U6") (pin "10") (pinfunction "PC2_10") (pintype "bidirectional"))
    )
    (net (code "33") (name "/SR_D2") (class "Default")
      (node (ref "P9") (pin "8") (pinfunction "D2_8") (pintype "passive"))
      (node (ref "U6") (pin "11") (pinfunction "PC3_11") (pintype "bidirectional"))
    )
    (net (code "34") (name "/SR_LED") (class "Default")
      (node (ref "P9") (pin "3") (pinfunction "LED_3") (pintype "passive"))
    )
    (net (code "35") (name "/SR_SW") (class "Default")
      (node (ref "P9") (pin "4") (pinfunction "SW_4") (pintype "passive"))
    )
    (net (code "36") (name "/SR_VT") (class "Default")
      (node (ref "P9") (pin "5") (pinfunction "VT_5") (pintype "passive"))
      (node (ref "U6") (pin "14") (pinfunction "PA0-WKUP_14") (pintype "bidirectional"))
    )
    (net (code "37") (name "/SWCLK") (class "Default")
      (node (ref "P11") (pin "3") (pinfunction "3_3") (pintype "passive"))
      (node (ref "U6") (pin "49") (pinfunction "PA14_49") (pintype "bidirectional"))
    )
    (net (code "38") (name "/SWDIO") (class "Default")
      (node (ref "P11") (pin "2") (pinfunction "2_2") (pintype "passive"))
      (node (ref "U6") (pin "46") (pinfunction "PA13_46") (pintype "bidirectional"))
    )
    (net (code "39") (name "/TTIM_IO") (class "Default")
      (node (ref "U6") (pin "22") (pinfunction "PA6_22") (pintype "bidirectional"))
      (node (ref "U9") (pin "6") (pinfunction "I/O_6") (pintype "passive"))
    )
    (net (code "40") (name "/TTIM_RSI") (class "Default")
      (node (ref "U6") (pin "23") (pinfunction "PA7_23") (pintype "bidirectional"))
      (node (ref "U9") (pin "5") (pinfunction "RSI_5") (pintype "passive"))
    )
    (net (code "41") (name "/TTIM_SCLK") (class "Default")
      (node (ref "U6") (pin "21") (pinfunction "PA5_21") (pintype "bidirectional"))
      (node (ref "U9") (pin "7") (pinfunction "SCLK_7") (pintype "passive"))
    )
    (net (code "42") (name "/Tem") (class "Default")
      (node (ref "R19") (pin "1") (pinfunction "1_1") (pintype "passive"))
      (node (ref "U6") (pin "39") (pinfunction "PC8_39") (pintype "bidirectional"))
      (node (ref "U8") (pin "2") (pinfunction "DQ_2") (pintype "passive"))
    )
    (net (code "43") (name "/WIFI_RX") (class "Default")
      (node (ref "U2") (pin "15") (pinfunction "RXD0_15") (pintype "passive"))
      (node (ref "U6") (pin "16") (pinfunction "PA2_16") (pintype "bidirectional"))
    )
    (net (code "44") (name "/WIFI_TX") (class "Default")
      (node (ref "U2") (pin "16") (pinfunction "TXD0_16") (pintype "passive"))
      (node (ref "U6") (pin "17") (pinfunction "PA3_17") (pintype "bidirectional"))
    )
    (net (code "45") (name "/YF_Busy") (class "Default")
      (node (ref "U6") (pin "2") (pinfunction "PC13-TAMPER-RTC_2") (pintype "bidirectional"))
      (node (ref "U7") (pin "8") (pinfunction "BUSY_8") (pintype "passive"))
    )
    (net (code "46") (name "/YF_Data") (class "Default")
      (node (ref "U6") (pin "3") (pinfunction "PC14-OSC32_IN_3") (pintype "bidirectional"))
      (node (ref "U7") (pin "7") (pinfunction "DATA_7") (pintype "passive"))
    )
    (net (code "47") (name "/YF_Reset") (class "Default")
      (node (ref "U6") (pin "4") (pinfunction "PC15-OSC32_OUT_4") (pintype "bidirectional"))
      (node (ref "U7") (pin "6") (pinfunction "RESET_6") (pintype "passive"))
    )
    (net (code "48") (name "Net-(BT1-+)") (class "Default")
      (node (ref "BT1") (pin "1") (pinfunction "+_1") (pintype "passive"))
      (node (ref "U9") (pin "8") (pinfunction "Vcc1_8") (pintype "passive"))
    )
    (net (code "49") (name "Net-(C11-Pad2)") (class "Default")
      (node (ref "C11") (pin "2") (pinfunction "2_2") (pintype "passive"))
      (node (ref "U7") (pin "1") (pinfunction "1_1") (pintype "passive"))
    )
    (net (code "50") (name "Net-(D1-A)") (class "Default")
      (node (ref "D1") (pin "1") (pinfunction "A_1") (pintype "passive"))
      (node (ref "R2") (pin "1") (pinfunction "1_1") (pintype "passive"))
    )
    (net (code "51") (name "Net-(D2-A)") (class "Default")
      (node (ref "C2") (pin "2") (pinfunction "2_2") (pintype "passive"))
      (node (ref "C21") (pin "2") (pinfunction "2_2") (pintype "passive"))
      (node (ref "D2") (pin "1") (pinfunction "A_1") (pintype "passive"))
      (node (ref "P5") (pin "2") (pinfunction "2_2") (pintype "passive"))
      (node (ref "Q1") (pin "2") (pinfunction "D_2") (pintype "passive"))
    )
    (net (code "52") (name "Net-(D3-A)") (class "Default")
      (node (ref "C9") (pin "2") (pinfunction "2_2") (pintype "passive"))
      (node (ref "D3") (pin "1") (pinfunction "A_1") (pintype "passive"))
      (node (ref "P8") (pin "2") (pinfunction "2_2") (pintype "passive"))
      (node (ref "Q6") (pin "2") (pinfunction "D_2") (pintype "passive"))
    )
    (net (code "53") (name "Net-(D4-A)") (class "Default")
      (node (ref "C10") (pin "2") (pinfunction "2_2") (pintype "passive"))
      (node (ref "D4") (pin "1") (pinfunction "A_1") (pintype "passive"))
      (node (ref "P10") (pin "2") (pinfunction "2_2") (pintype "passive"))
      (node (ref "Q8") (pin "2") (pinfunction "D_2") (pintype "passive"))
    )
    (net (code "54") (name "Net-(P13-Pad1)") (class "Default")
      (node (ref "P13") (pin "1") (pinfunction "1_1") (pintype "passive"))
      (node (ref "U7") (pin "2") (pinfunction "2_2") (pintype "passive"))
    )
    (net (code "55") (name "Net-(P13-Pad2)") (class "Default")
      (node (ref "P13") (pin "2") (pinfunction "2_2") (pintype "passive"))
      (node (ref "U7") (pin "3") (pinfunction "3_3") (pintype "passive"))
    )
    (net (code "56") (name "Net-(P16-Pad1)") (class "Default")
      (node (ref "P16") (pin "1") (pinfunction "1_1") (pintype "passive"))
      (node (ref "R26") (pin "1") (pinfunction "1_1") (pintype "passive"))
    )
    (net (code "57") (name "Net-(Q1-G)") (class "Default")
      (node (ref "Q1") (pin "1") (pinfunction "G_1") (pintype "passive"))
      (node (ref "Q2") (pin "3") (pinfunction "C_3") (pintype "passive"))
      (node (ref "R4") (pin "2") (pinfunction "2_2") (pintype "passive"))
    )
    (net (code "58") (name "Net-(Q2-B)") (class "Default")
      (node (ref "Q2") (pin "1") (pinfunction "B_1") (pintype "passive"))
      (node (ref "R6") (pin "2") (pinfunction "2_2") (pintype "passive"))
    )
    (net (code "59") (name "Net-(Q3-D)") (class "Default")
      (node (ref "P7") (pin "2") (pinfunction "2_2") (pintype "passive"))
      (node (ref "Q3") (pin "2") (pinfunction "D_2") (pintype "passive"))
    )
    (net (code "60") (name "Net-(Q3-G)") (class "Default")
      (node (ref "Q3") (pin "1") (pinfunction "G_1") (pintype "passive"))
      (node (ref "Q4") (pin "3") (pinfunction "C_3") (pintype "passive"))
      (node (ref "R7") (pin "2") (pinfunction "2_2") (pintype "passive"))
    )
    (net (code "61") (name "Net-(Q4-B)") (class "Default")
      (node (ref "Q4") (pin "1") (pinfunction "B_1") (pintype "passive"))
      (node (ref "R8") (pin "2") (pinfunction "2_2") (pintype "passive"))
    )
    (net (code "62") (name "Net-(Q5-B)") (class "Default")
      (node (ref "Q5") (pin "1") (pinfunction "B_1") (pintype "passive"))
      (node (ref "R10") (pin "1") (pinfunction "1_1") (pintype "passive"))
    )
    (net (code "63") (name "Net-(Q5-C)") (class "Default")
      (node (ref "LS1") (pin "2") (pinfunction "2_2") (pintype "passive"))
      (node (ref "Q5") (pin "3") (pinfunction "C_3") (pintype "passive"))
    )
    (net (code "64") (name "Net-(Q6-G)") (class "Default")
      (node (ref "Q6") (pin "1") (pinfunction "G_1") (pintype "passive"))
      (node (ref "Q7") (pin "3") (pinfunction "C_3") (pintype "passive"))
      (node (ref "R12") (pin "2") (pinfunction "2_2") (pintype "passive"))
    )
    (net (code "65") (name "Net-(Q7-B)") (class "Default")
      (node (ref "Q7") (pin "1") (pinfunction "B_1") (pintype "passive"))
      (node (ref "R13") (pin "2") (pinfunction "2_2") (pintype "passive"))
    )
    (net (code "66") (name "Net-(Q8-G)") (class "Default")
      (node (ref "Q8") (pin "1") (pinfunction "G_1") (pintype "passive"))
      (node (ref "Q9") (pin "3") (pinfunction "C_3") (pintype "passive"))
      (node (ref "R16") (pin "2") (pinfunction "2_2") (pintype "passive"))
    )
    (net (code "67") (name "Net-(Q9-B)") (class "Default")
      (node (ref "Q9") (pin "1") (pinfunction "B_1") (pintype "passive"))
      (node (ref "R17") (pin "2") (pinfunction "2_2") (pintype "passive"))
    )
    (net (code "68") (name "Net-(U2-CH_PD)") (class "Default")
      (node (ref "R9") (pin "1") (pinfunction "1_1") (pintype "passive"))
      (node (ref "U2") (pin "3") (pinfunction "CH_PD_3") (pintype "passive"))
    )
    (net (code "69") (name "Net-(U2-GPIO15)") (class "Default")
      (node (ref "R11") (pin "1") (pinfunction "1_1") (pintype "passive"))
      (node (ref "U2") (pin "10") (pinfunction "GPIO15_10") (pintype "passive"))
    )
    (net (code "70") (name "Net-(U6A-BOOT0)") (class "Default")
      (node (ref "R25") (pin "2") (pinfunction "2_2") (pintype "passive"))
      (node (ref "U6") (pin "60") (pinfunction "BOOT0_60") (pintype "input"))
    )
    (net (code "71") (name "Net-(U6A-NRST)") (class "Default")
      (node (ref "C23") (pin "2") (pinfunction "2_2") (pintype "passive"))
      (node (ref "R31") (pin "2") (pinfunction "2_2") (pintype "passive"))
      (node (ref "S1") (pin "2") (pinfunction "2_2") (pintype "passive"))
      (node (ref "U6") (pin "7") (pinfunction "NRST_7") (pintype "bidirectional"))
    )
    (net (code "72") (name "Net-(U6A-PD0-OSC_IN)") (class "Default")
      (node (ref "C14") (pin "1") (pinfunction "1_1") (pintype "passive"))
      (node (ref "U6") (pin "5") (pinfunction "PD0-OSC_IN_5") (pintype "bidirectional"))
      (node (ref "Y1") (pin "2") (pinfunction "OSC2_2") (pintype "passive"))
    )
    (net (code "73") (name "Net-(U6A-PD1)") (class "Default")
      (node (ref "C15") (pin "1") (pinfunction "1_1") (pintype "passive"))
      (node (ref "U6") (pin "6") (pinfunction "PD1_6") (pintype "bidirectional"))
      (node (ref "Y1") (pin "1") (pinfunction "OSC1_1") (pintype "passive"))
    )
    (net (code "74") (name "Net-(U9-X1)") (class "Default")
      (node (ref "C18") (pin "2") (pinfunction "2_2") (pintype "passive"))
      (node (ref "U9") (pin "2") (pinfunction "X1_2") (pintype "passive"))
      (node (ref "Y2") (pin "2") (pinfunction "OSC2_2") (pintype "passive"))
    )
    (net (code "75") (name "Net-(U9-X2)") (class "Default")
      (node (ref "C19") (pin "2") (pinfunction "2_2") (pintype "passive"))
      (node (ref "U9") (pin "3") (pinfunction "X2_3") (pintype "passive"))
      (node (ref "Y2") (pin "1") (pinfunction "OSC1_1") (pintype "passive"))
    )
    (net (code "76") (name "Net-(U10A-INA+)") (class "Default")
      (node (ref "R26") (pin "2") (pinfunction "2_2") (pintype "passive"))
      (node (ref "U10") (pin "3") (pinfunction "INA+_3") (pintype "input"))
    )
    (net (code "77") (name "Net-(U10A-INA-)") (class "Default")
      (node (ref "R27") (pin "1") (pinfunction "1_1") (pintype "passive"))
      (node (ref "R30") (pin "2") (pinfunction "2_2") (pintype "passive"))
      (node (ref "U10") (pin "2") (pinfunction "INA-_2") (pintype "input"))
    )
    (net (code "78") (name "Net-(U10A-OUTA)") (class "Default")
      (node (ref "R27") (pin "2") (pinfunction "2_2") (pintype "passive"))
      (node (ref "R28") (pin "2") (pinfunction "2_2") (pintype "passive"))
      (node (ref "U10") (pin "1") (pinfunction "OUTA_1") (pintype "output"))
    )
    (net (code "79") (name "PGND") (class "Default")
      (node (ref "C1") (pin "2") (pinfunction "2_2") (pintype "passive"))
      (node (ref "C11") (pin "1") (pinfunction "1_1") (pintype "passive"))
      (node (ref "C5") (pin "2") (pinfunction "2_2") (pintype "passive"))
      (node (ref "C6") (pin "2") (pinfunction "2_2") (pintype "passive"))
      (node (ref "D1") (pin "2") (pinfunction "K_2") (pintype "passive"))
      (node (ref "P1") (pin "3") (pinfunction "3_3") (pintype "passive"))
      (node (ref "P14") (pin "3") (pinfunction "3_3") (pintype "passive"))
      (node (ref "P15") (pin "3") (pinfunction "3_3") (pintype "passive"))
      (node (ref "P16") (pin "2") (pinfunction "2_2") (pintype "passive"))
      (node (ref "P2") (pin "3") (pinfunction "3_3") (pintype "passive"))
      (node (ref "P3") (pin "2") (pinfunction "2_2") (pintype "passive"))
      (node (ref "P4") (pin "3") (pinfunction "3_3") (pintype "passive"))
      (node (ref "P6") (pin "7") (pinfunction "7_7") (pintype "passive"))
      (node (ref "Q1") (pin "3") (pinfunction "S_3") (pintype "passive"))
      (node (ref "Q3") (pin "3") (pinfunction "S_3") (pintype "passive"))
      (node (ref "Q5") (pin "2") (pinfunction "E_2") (pintype "passive"))
      (node (ref "Q6") (pin "3") (pinfunction "S_3") (pintype "passive"))
      (node (ref "Q8") (pin "3") (pinfunction "S_3") (pintype "passive"))
      (node (ref "R1") (pin "1") (pinfunction "1_1") (pintype "passive"))
      (node (ref "R29") (pin "1") (pinfunction "1_1") (pintype "passive"))
      (node (ref "R3") (pin "2") (pinfunction "2_2") (pintype "passive"))
      (node (ref "R30") (pin "1") (pinfunction "1_1") (pintype "passive"))
      (node (ref "R5") (pin "2") (pinfunction "TAP_2") (pintype "passive"))
      (node (ref "U1") (pin "5") (pinfunction "H_5") (pintype "passive"))
      (node (ref "U10") (pin "8") (pinfunction "V+_8") (pintype "power_in"))
      (node (ref "U3") (pin "2") (pinfunction "GND_2") (pintype "power_in"))
      (node (ref "U7") (pin "5") (pinfunction "GND_5") (pintype "passive"))
    )
    (net (code "80") (name "SGND") (class "Default")
      (node (ref "BT1") (pin "2") (pinfunction "-_2") (pintype "passive"))
      (node (ref "C14") (pin "2") (pinfunction "2_2") (pintype "passive"))
      (node (ref "C15") (pin "2") (pinfunction "2_2") (pintype "passive"))
      (node (ref "C18") (pin "1") (pinfunction "1_1") (pintype "passive"))
      (node (ref "C19") (pin "1") (pinfunction "1_1") (pintype "passive"))
      (node (ref "C20") (pin "2") (pinfunction "2_2") (pintype "passive"))
      (node (ref "C22") (pin "2") (pinfunction "2_2") (pintype "passive"))
      (node (ref "C23") (pin "1") (pinfunction "1_1") (pintype "passive"))
      (node (ref "C24") (pin "2") (pinfunction "2_2") (pintype "passive"))
      (node (ref "C26") (pin "2") (pinfunction "2_2") (pintype "passive"))
      (node (ref "C3") (pin "2") (pinfunction "2_2") (pintype "passive"))
      (node (ref "C4") (pin "2") (pinfunction "2_2") (pintype "passive"))
      (node (ref "C7") (pin "2") (pinfunction "2_2") (pintype "passive"))
      (node (ref "C8") (pin "2") (pinfunction "2_2") (pintype "passive"))
      (node (ref "P11") (pin "4") (pinfunction "4_4") (pintype "passive"))
      (node (ref "P12") (pin "4") (pinfunction "4_4") (pintype "passive"))
      (node (ref "P9") (pin "11") (pinfunction "GND_11") (pintype "passive"))
      (node (ref "P9") (pin "2") (pinfunction "GND_2") (pintype "passive"))
      (node (ref "Q2") (pin "2") (pinfunction "E_2") (pintype "passive"))
      (node (ref "Q4") (pin "2") (pinfunction "E_2") (pintype "passive"))
      (node (ref "Q7") (pin "2") (pinfunction "E_2") (pintype "passive"))
      (node (ref "Q9") (pin "2") (pinfunction "E_2") (pintype "passive"))
      (node (ref "R1") (pin "2") (pinfunction "2_2") (pintype "passive"))
      (node (ref "R11") (pin "2") (pinfunction "2_2") (pintype "passive"))
      (node (ref "R18") (pin "1") (pinfunction "1_1") (pintype "passive"))
      (node (ref "R22") (pin "1") (pinfunction "A0_1") (pintype "passive"))
      (node (ref "R22") (pin "2") (pinfunction "A1_2") (pintype "passive"))
      (node (ref "R22") (pin "3") (pinfunction "A2_3") (pintype "passive"))
      (node (ref "R22") (pin "4") (pinfunction "GND_4") (pintype "passive"))
      (node (ref "R22") (pin "7") (pinfunction "WP_7") (pintype "passive"))
      (node (ref "S1") (pin "1") (pinfunction "1_1") (pintype "passive"))
      (node (ref "U2") (pin "9") (pinfunction "GND_9") (pintype "passive"))
      (node (ref "U4") (pin "1") (pinfunction "Ground_1") (pintype "passive"))
      (node (ref "U5") (pin "1") (pinfunction "RESERVED_1") (pintype "passive"))
      (node (ref "U5") (pin "4") (pinfunction "AVSS_4") (pintype "passive"))
      (node (ref "U5") (pin "8") (pinfunction "DVSS_8") (pintype "passive"))
      (node (ref "U6") (pin "12") (pinfunction "VSSA_12") (pintype "power_in"))
      (node (ref "U6") (pin "18") (pinfunction "VSS_4_18") (pintype "power_in"))
      (node (ref "U6") (pin "31") (pinfunction "VSS_1_31") (pintype "power_in"))
      (node (ref "U6") (pin "47") (pinfunction "VSS_2_47") (pintype "power_in"))
      (node (ref "U6") (pin "63") (pinfunction "VSS_3_63") (pintype "power_in"))
      (node (ref "U8") (pin "1") (pinfunction "GND_1") (pintype "passive"))
      (node (ref "U9") (pin "4") (pinfunction "GND_4") (pintype "passive"))
    )
    (net (code "81") (name "unconnected-(P9-ANT-Pad1)") (class "Default")
      (node (ref "P9") (pin "1") (pinfunction "ANT_1") (pintype "passive"))
    )
    (net (code "82") (name "unconnected-(P9-D3-Pad9)") (class "Default")
      (node (ref "P9") (pin "9") (pinfunction "D3_9") (pintype "passive"))
    )
    (net (code "83") (name "unconnected-(R5-BOT-Pad3)") (class "Default")
      (node (ref "R5") (pin "3") (pinfunction "BOT_3") (pintype "passive"))
    )
    (net (code "84") (name "unconnected-(U1-A-Pad3)") (class "Default")
      (node (ref "U1") (pin "3") (pinfunction "A_3") (pintype "passive"))
    )
    (net (code "85") (name "unconnected-(U1-B-Pad4)") (class "Default")
      (node (ref "U1") (pin "4") (pinfunction "B_4") (pintype "passive"))
    )
    (net (code "86") (name "unconnected-(U2-ADC-Pad2)") (class "Default")
      (node (ref "U2") (pin "2") (pinfunction "ADC_2") (pintype "passive"))
    )
    (net (code "87") (name "unconnected-(U2-GPIO0-Pad12)") (class "Default")
      (node (ref "U2") (pin "12") (pinfunction "GPIO0_12") (pintype "passive"))
    )
    (net (code "88") (name "unconnected-(U2-GPIO2-Pad11)") (class "Default")
      (node (ref "U2") (pin "11") (pinfunction "GPIO2_11") (pintype "passive"))
    )
    (net (code "89") (name "unconnected-(U2-GPIO4-Pad14)") (class "Default")
      (node (ref "U2") (pin "14") (pinfunction "GPIO4_14") (pintype "passive"))
    )
    (net (code "90") (name "unconnected-(U2-GPIO5-Pad13)") (class "Default")
      (node (ref "U2") (pin "13") (pinfunction "GPIO5_13") (pintype "passive"))
    )
    (net (code "91") (name "unconnected-(U2-GPIO12-Pad6)") (class "Default")
      (node (ref "U2") (pin "6") (pinfunction "GPIO12_6") (pintype "passive"))
    )
    (net (code "92") (name "unconnected-(U2-GPIO13-Pad7)") (class "Default")
      (node (ref "U2") (pin "7") (pinfunction "GPIO13_7") (pintype "passive"))
    )
    (net (code "93") (name "unconnected-(U2-GPIO14-Pad5)") (class "Default")
      (node (ref "U2") (pin "5") (pinfunction "GPIO14_5") (pintype "passive"))
    )
    (net (code "94") (name "unconnected-(U2-GPIO16-Pad4)") (class "Default")
      (node (ref "U2") (pin "4") (pinfunction "GPIO16_4") (pintype "passive"))
    )
    (net (code "95") (name "unconnected-(U5-INT-Pad5)") (class "Default")
      (node (ref "U5") (pin "5") (pinfunction "INT_5") (pintype "passive"))
    )
    (net (code "96") (name "unconnected-(U5-NC-Pad10)") (class "Default")
      (node (ref "U5") (pin "10") (pinfunction "NC_10") (pintype "passive"))
    )
    (net (code "97") (name "unconnected-(U5-N{slash}C-Pad2)") (class "Default")
      (node (ref "U5") (pin "2") (pinfunction "N/C_2") (pintype "passive"))
    )
    (net (code "98") (name "unconnected-(U6A-PA9-Pad42)") (class "Default")
      (node (ref "U6") (pin "42") (pinfunction "PA9_42") (pintype "bidirectional"))
    )
    (net (code "99") (name "unconnected-(U6A-PA10-Pad43)") (class "Default")
      (node (ref "U6") (pin "43") (pinfunction "PA10_43") (pintype "bidirectional"))
    )
    (net (code "100") (name "unconnected-(U6A-PB8-Pad61)") (class "Default")
      (node (ref "U6") (pin "61") (pinfunction "PB8_61") (pintype "bidirectional"))
    )
    (net (code "101") (name "unconnected-(U6A-PC4-Pad24)") (class "Default")
      (node (ref "U6") (pin "24") (pinfunction "PC4_24") (pintype "bidirectional"))
    )
    (net (code "102") (name "unconnected-(U6A-PC5-Pad25)") (class "Default")
      (node (ref "U6") (pin "25") (pinfunction "PC5_25") (pintype "bidirectional"))
    )
    (net (code "103") (name "unconnected-(U6A-PC9-Pad40)") (class "Default")
      (node (ref "U6") (pin "40") (pinfunction "PC9_40") (pintype "bidirectional"))
    )
    (net (code "104") (name "unconnected-(U6A-PD2-Pad54)") (class "Default")
      (node (ref "U6") (pin "54") (pinfunction "PD2_54") (pintype "bidirectional"))
    )
    (net (code "105") (name "unconnected-(U6B-VBAT-Pad1)") (class "Default")
      (node (ref "U6") (pin "1") (pinfunction "VBAT_1") (pintype "power_in"))
    )
  )
)
